# Sheet7.net
KiCad netlist of a schematic drawn in Altium Designer
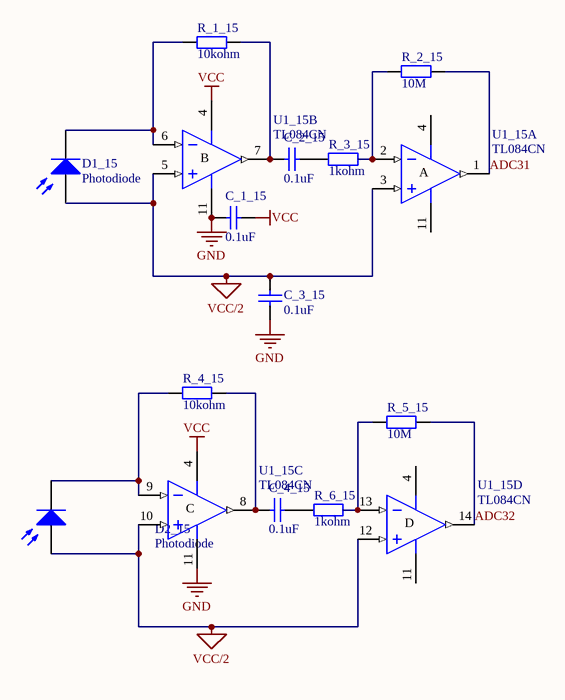
[diagram p0: Sheet7.SchDoc]

(export (version "E")
  (design (tool "Eeschema 10.0.6"))
  (components
    (comp (ref "C_1_15")
      (value "0.1uF")
      (footprint "cms805 - mini")
      (libsource (lib "lib_Robotronik") (part "Capa"))
    )
    (comp (ref "C_2_15")
      (value "0.1uF")
      (footprint "cms805 - mini")
      (libsource (lib "lib_Robotronik") (part "Capa"))
    )
    (comp (ref "C_3_15")
      (value "0.1uF")
      (footprint "cms805 - mini")
      (libsource (lib "lib_Robotronik") (part "Capa"))
    )
    (comp (ref "C_4_15")
      (value "0.1uF")
      (footprint "cms805 - mini")
      (libsource (lib "lib_Robotronik") (part "Capa"))
    )
    (comp (ref "D1_15")
      (value "Photodiode")
      (footprint "TEMD1000")
      (fields (field (name "PUBLISHER") "Altium Limited"))
      (libsource (lib "lib_Robotronik") (part "Photodiode"))
    )
    (comp (ref "D2_15")
      (value "Photodiode")
      (footprint "TEMD1000")
      (fields (field (name "PUBLISHER") "Altium Limited"))
      (libsource (lib "lib_Robotronik") (part "Photodiode"))
    )
    (comp (ref "R_1_15")
      (value "10kohm")
      (footprint "cms805 - mini")
      (libsource (lib "lib_Robotronik") (part "Resistance"))
    )
    (comp (ref "R_2_15")
      (value "10M")
      (footprint "cms805 - mini")
      (libsource (lib "lib_Robotronik") (part "Resistance"))
    )
    (comp (ref "R_3_15")
      (value "1kohm")
      (footprint "cms805 - mini")
      (libsource (lib "lib_Robotronik") (part "Resistance"))
    )
    (comp (ref "R_4_15")
      (value "10kohm")
      (footprint "cms805 - mini")
      (libsource (lib "lib_Robotronik") (part "Resistance"))
    )
    (comp (ref "R_5_15")
      (value "10M")
      (footprint "cms805 - mini")
      (libsource (lib "lib_Robotronik") (part "Resistance"))
    )
    (comp (ref "R_6_15")
      (value "1kohm")
      (footprint "cms805 - mini")
      (libsource (lib "lib_Robotronik") (part "Resistance"))
    )
    (comp (ref "U1_15")
      (value "TL084CN")
      (footprint "TSSOP14")
      (description "General-Purpose J-FET Quad Operational Amplifier")
      (fields (field (name "PUBLISHER") "Altium Limited"))
      (libsource (lib "lib_Robotronik") (part "TL084CN"))
    )
  )
  (nets
    (net (code "1") (name "/ADC31") (class "Default")
      (node (ref "R_2_15") (pin "2") (pinfunction "2_2") (pintype "passive"))
      (node (ref "U1_15") (pin "1") (pinfunction "OUT_1") (pintype "output"))
    )
    (net (code "2") (name "/ADC32") (class "Default")
      (node (ref "R_5_15") (pin "2") (pinfunction "2_2") (pintype "passive"))
      (node (ref "U1_15") (pin "14") (pinfunction "OUT_14") (pintype "output"))
    )
    (net (code "3") (name "GND") (class "Default")
      (node (ref "C_1_15") (pin "1") (pinfunction "1_1") (pintype "passive"))
      (node (ref "C_3_15") (pin "1") (pinfunction "1_1") (pintype "passive"))
      (node (ref "U1_15") (pin "11") (pinfunction "V-_11") (pintype "power_in"))
    )
    (net (code "4") (name "Net-(C_2_15-Pad1)") (class "Default")
      (node (ref "C_2_15") (pin "1") (pinfunction "1_1") (pintype "passive"))
      (node (ref "R_3_15") (pin "1") (pinfunction "1_1") (pintype "passive"))
    )
    (net (code "5") (name "Net-(C_4_15-Pad1)") (class "Default")
      (node (ref "C_4_15") (pin "1") (pinfunction "1_1") (pintype "passive"))
      (node (ref "R_6_15") (pin "1") (pinfunction "1_1") (pintype "passive"))
    )
    (net (code "6") (name "Net-(D1_15-K)") (class "Default")
      (node (ref "D1_15") (pin "2") (pinfunction "K_2") (pintype "passive"))
      (node (ref "R_1_15") (pin "1") (pinfunction "1_1") (pintype "passive"))
      (node (ref "U1_15") (pin "6") (pinfunction "IN-_6") (pintype "input"))
    )
    (net (code "7") (name "Net-(D2_15-K)") (class "Default")
      (node (ref "D2_15") (pin "2") (pinfunction "K_2") (pintype "passive"))
      (node (ref "R_4_15") (pin "1") (pinfunction "1_1") (pintype "passive"))
      (node (ref "U1_15") (pin "9") (pinfunction "IN-_9") (pintype "input"))
    )
    (net (code "8") (name "Net-(U1_15A-IN-)") (class "Default")
      (node (ref "R_2_15") (pin "1") (pinfunction "1_1") (pintype "passive"))
      (node (ref "R_3_15") (pin "2") (pinfunction "2_2") (pintype "passive"))
      (node (ref "U1_15") (pin "2") (pinfunction "IN-_2") (pintype "input"))
    )
    (net (code "9") (name "Net-(U1_15B-OUT)") (class "Default")
      (node (ref "C_2_15") (pin "2") (pinfunction "2_2") (pintype "passive"))
      (node (ref "R_1_15") (pin "2") (pinfunction "2_2") (pintype "passive"))
      (node (ref "U1_15") (pin "7") (pinfunction "OUT_7") (pintype "output"))
    )
    (net (code "10") (name "Net-(U1_15C-OUT)") (class "Default")
      (node (ref "C_4_15") (pin "2") (pinfunction "2_2") (pintype "passive"))
      (node (ref "R_4_15") (pin "2") (pinfunction "2_2") (pintype "passive"))
      (node (ref "U1_15") (pin "8") (pinfunction "OUT_8") (pintype "output"))
    )
    (net (code "11") (name "Net-(U1_15D-IN-)") (class "Default")
      (node (ref "R_5_15") (pin "1") (pinfunction "1_1") (pintype "passive"))
      (node (ref "R_6_15") (pin "2") (pinfunction "2_2") (pintype "passive"))
      (node (ref "U1_15") (pin "13") (pinfunction "IN-_13") (pintype "input"))
    )
    (net (code "12") (name "VCC") (class "Default")
      (node (ref "C_1_15") (pin "2") (pinfunction "2_2") (pintype "passive"))
      (node (ref "U1_15") (pin "4") (pinfunction "V+_4") (pintype "power_in"))
    )
    (net (code "13") (name "VCC{slash}2") (class "Default")
      (node (ref "C_3_15") (pin "2") (pinfunction "2_2") (pintype "passive"))
      (node (ref "D1_15") (pin "1") (pinfunction "A_1") (pintype "passive"))
      (node (ref "D2_15") (pin "1") (pinfunction "A_1") (pintype "passive"))
      (node (ref "U1_15") (pin "10") (pinfunction "IN+_10") (pintype "input"))
      (node (ref "U1_15") (pin "12") (pinfunction "IN+_12") (pintype "input"))
      (node (ref "U1_15") (pin "3") (pinfunction "IN+_3") (pintype "input"))
      (node (ref "U1_15") (pin "5") (pinfunction "IN+_5") (pintype "input"))
    )
    (net (code "14") (name "unconnected-(U1_15A-V+-Pad4)") (class "Default")
      (node (ref "U1_15") (pin "4") (pinfunction "V+_4") (pintype "power_in"))
    )
    (net (code "15") (name "unconnected-(U1_15A-V--Pad11)") (class "Default")
      (node (ref "U1_15") (pin "11") (pinfunction "V-_11") (pintype "power_in"))
    )
    (net (code "16") (name "unconnected-(U1_15D-V+-Pad4)") (class "Default")
      (node (ref "U1_15") (pin "4") (pinfunction "V+_4") (pintype "power_in"))
    )
    (net (code "17") (name "unconnected-(U1_15D-V--Pad11)") (class "Default")
      (node (ref "U1_15") (pin "11") (pinfunction "V-_11") (pintype "power_in"))
    )
  )
)
